# HW-DC25-Badge-20170609-1_2.net
KiCad netlist of a schematic drawn in EAGLE
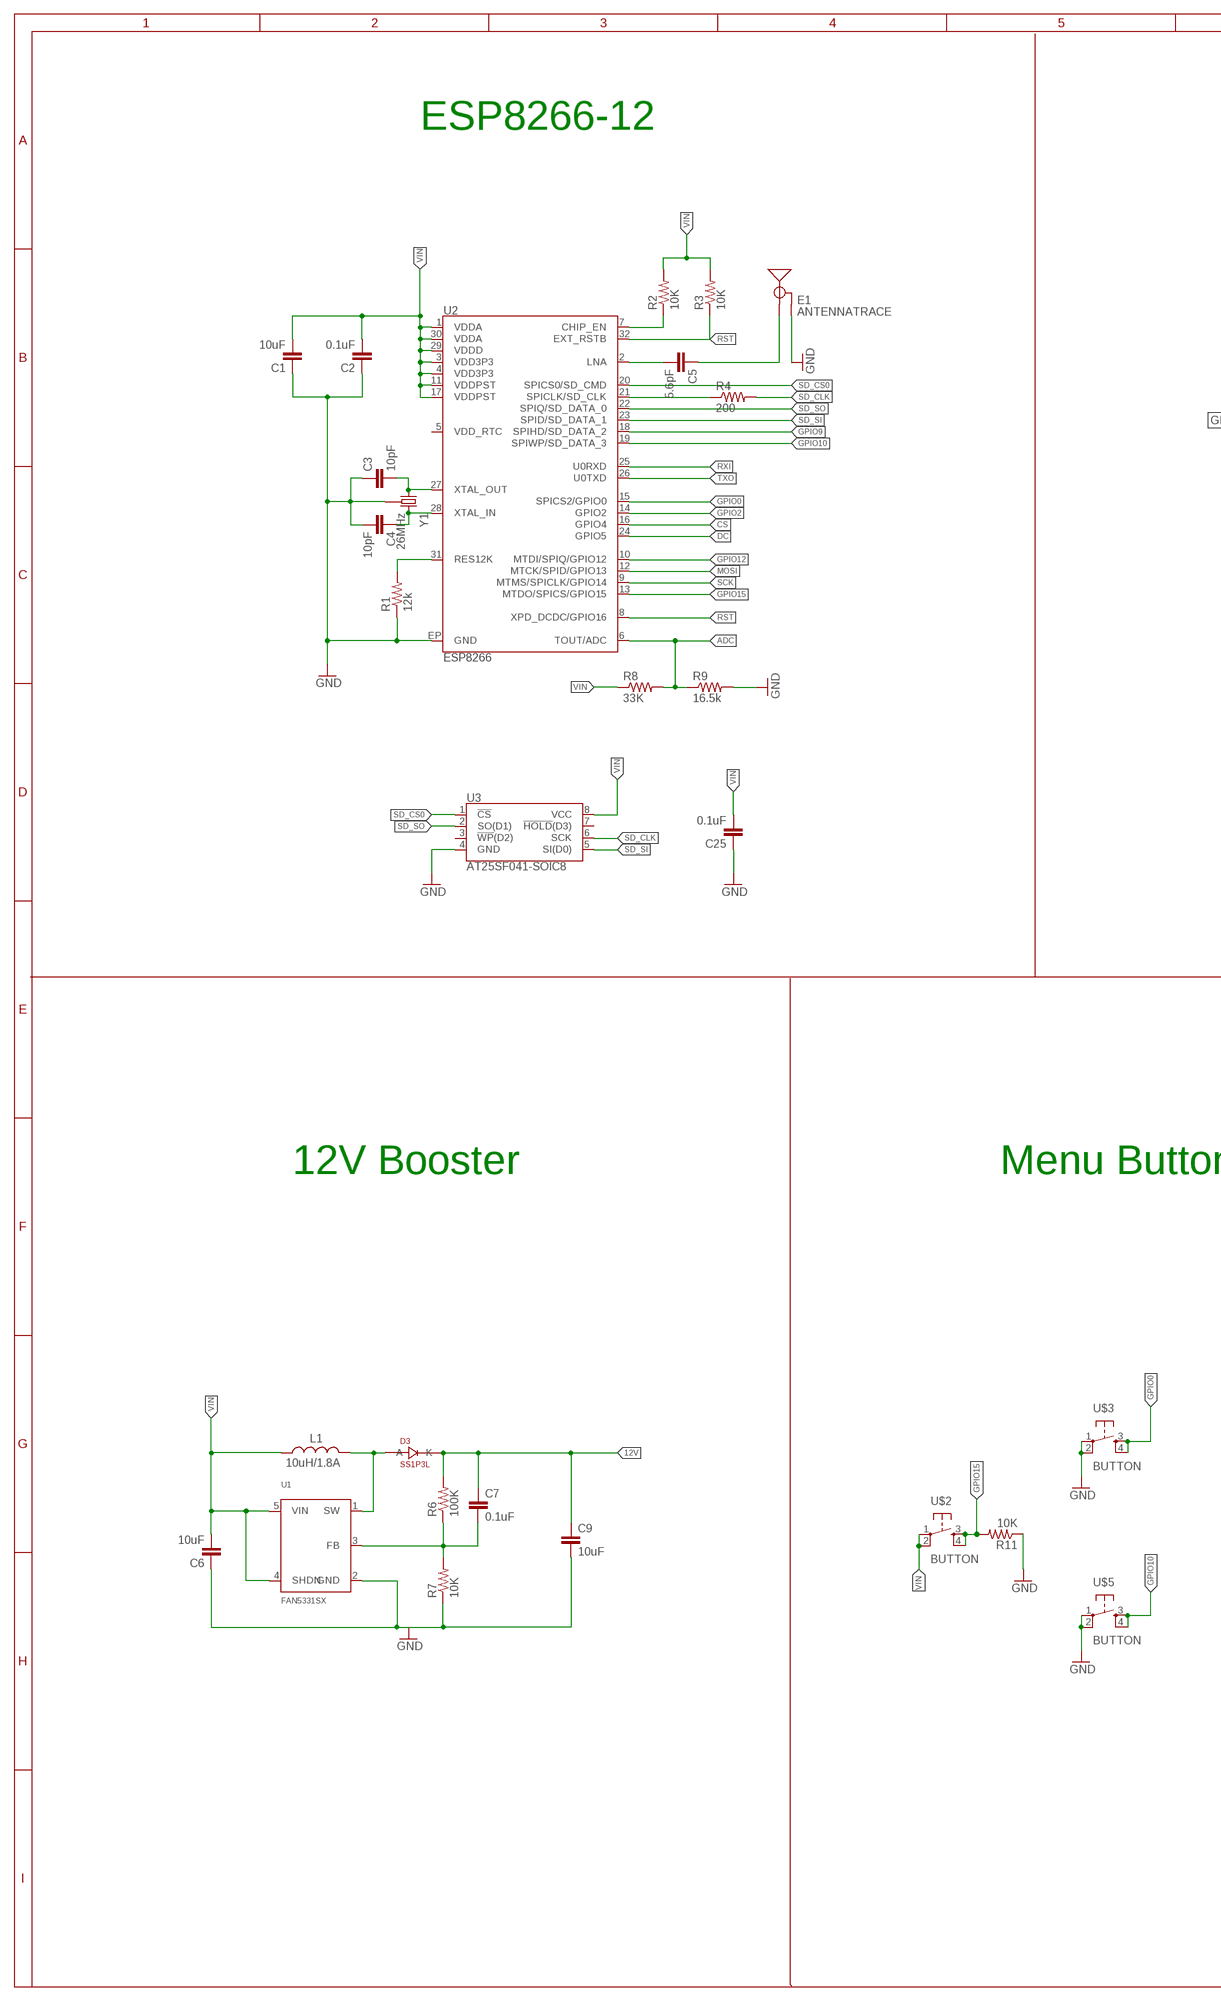
[diagram p0: schematic, sheet 1, part 1 of 2]
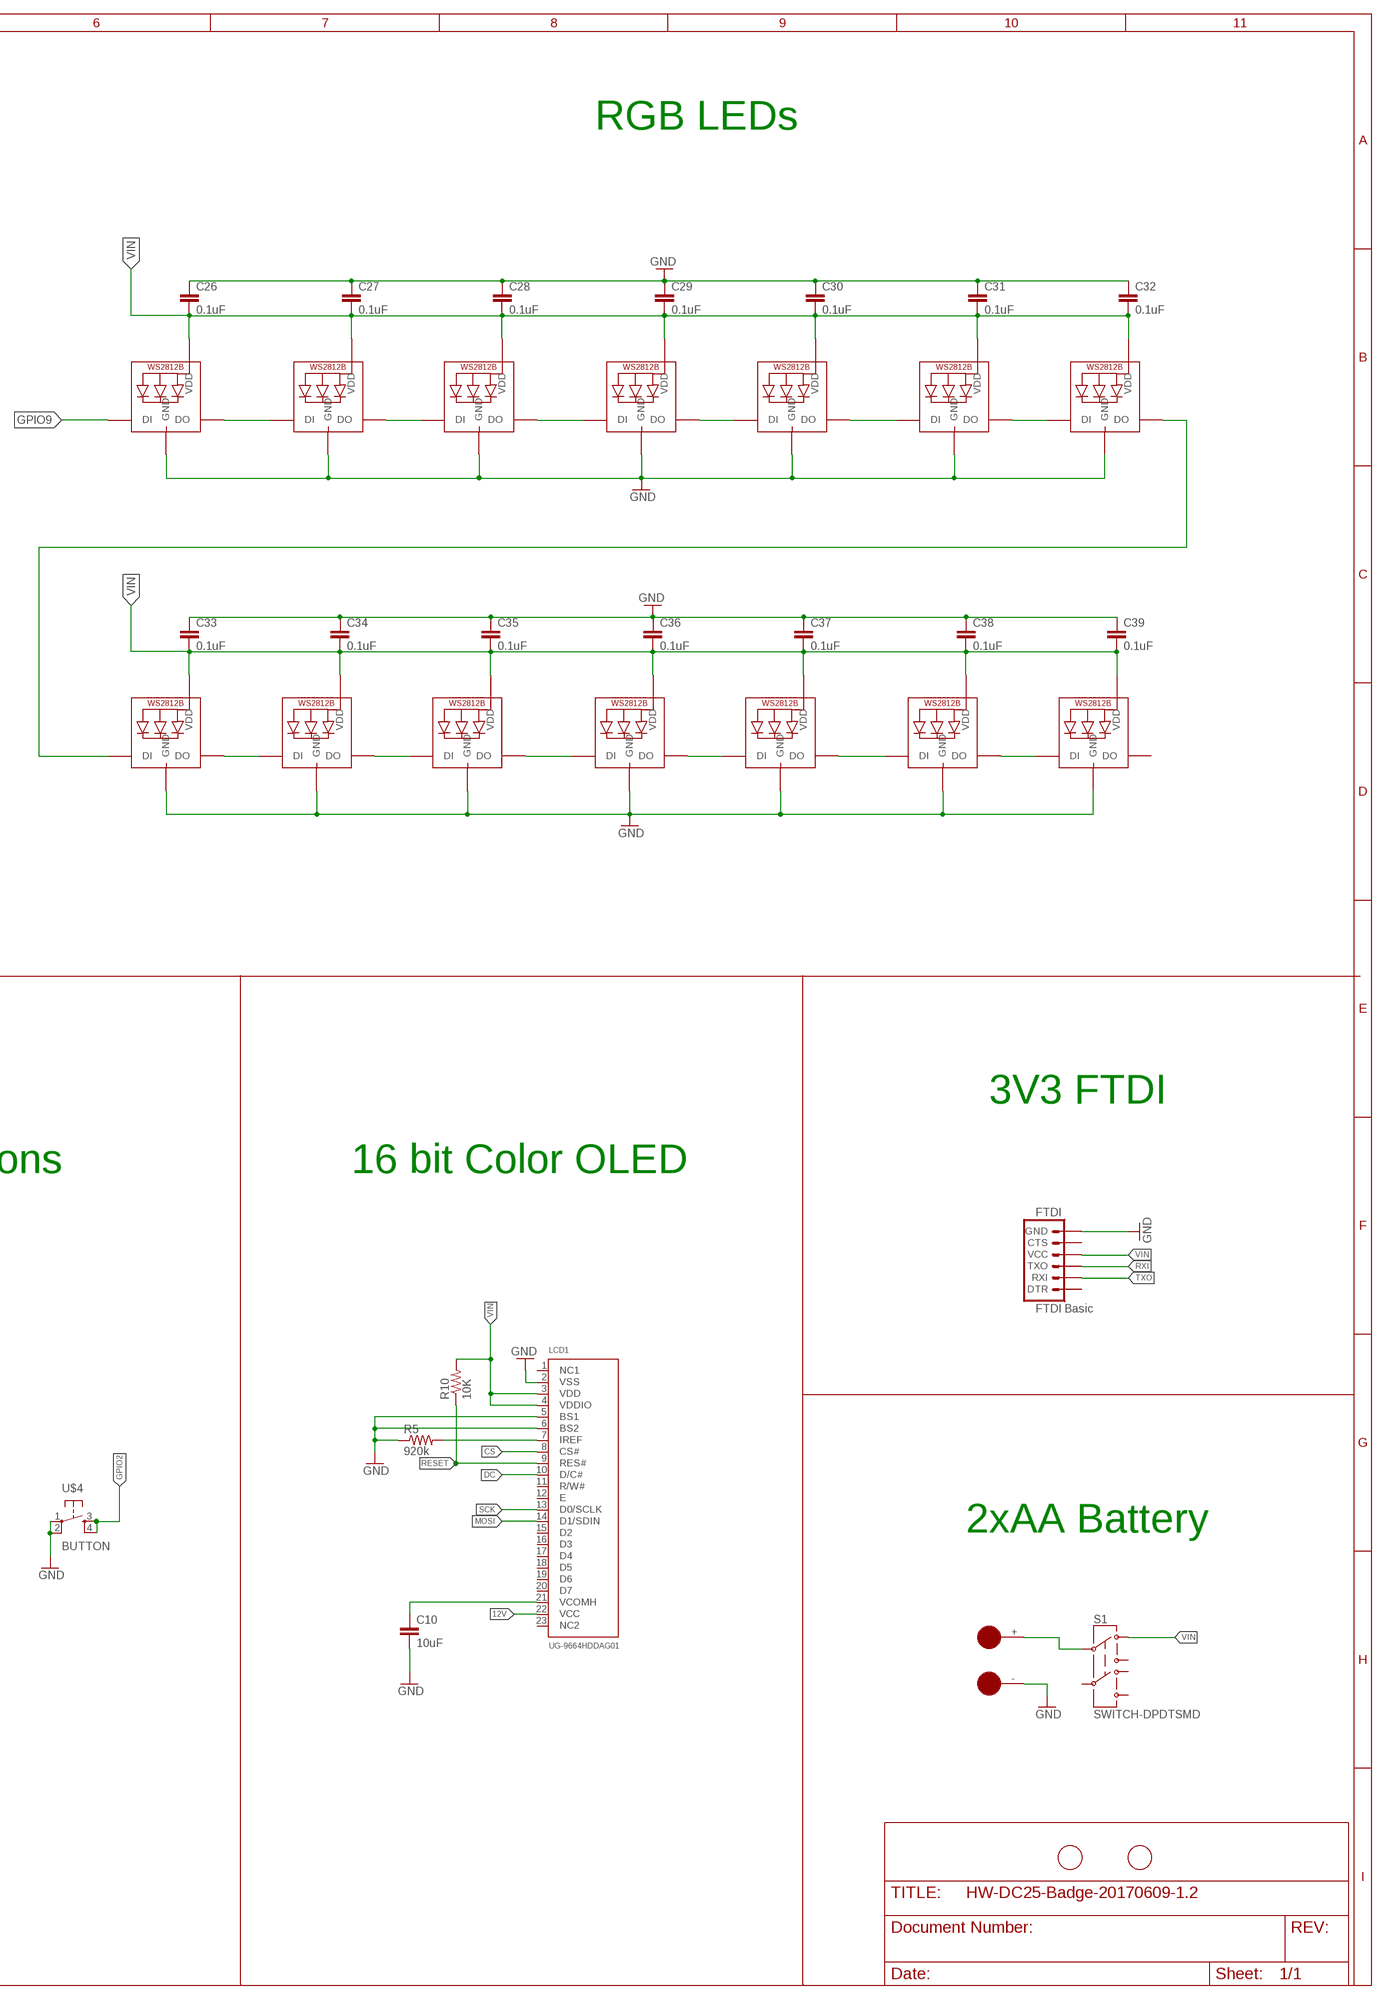
[diagram p1: schematic, sheet 1, part 2 of 2]

(export (version "E")
  (design (tool "Eeschema 10.0.6"))
  (components
    (comp (ref "C1")
      (value "10uF")
      (footprint "eagle-import:CAP0603")
      (fields (field (name "TOLERANCE") "10%") (field (name "VOLTAGE") "10V"))
      (libsource (lib "eagle-import") (part "CAP-0603-10UF-10V-10%"))
    )
    (comp (ref "C2")
      (value "0.1uF")
      (footprint "eagle-import:CAP0603")
      (fields (field (name "TOLERANCE") "10%") (field (name "VOLTAGE") "10V"))
      (libsource (lib "eagle-import") (part "CAP-0603-10UF-10V-10%"))
    )
    (comp (ref "C3")
      (value "10pF")
      (footprint "eagle-import:CAP0603")
      (fields (field (name "TOLERANCE") "10%") (field (name "VOLTAGE") "50V"))
      (libsource (lib "eagle-import") (part "CAP-0603-0.01UF-50V-10%"))
    )
    (comp (ref "C4")
      (value "10pF")
      (footprint "eagle-import:CAP0603")
      (fields (field (name "TOLERANCE") "10%") (field (name "VOLTAGE") "50V"))
      (libsource (lib "eagle-import") (part "CAP-0603-0.01UF-50V-10%"))
    )
    (comp (ref "C5")
      (value "5.6pF")
      (footprint "eagle-import:CAP0603")
      (libsource (lib "eagle-import") (part "CAP-0603-EMPTY-VALUES"))
    )
    (comp (ref "C6")
      (value "10uF")
      (footprint "eagle-import:CAP0603")
      (fields (field (name "TOLERANCE") "10%") (field (name "VOLTAGE") "10V"))
      (libsource (lib "eagle-import") (part "CAP-0603-10UF-10V-10%"))
    )
    (comp (ref "C7")
      (value "0.1uF")
      (footprint "eagle-import:CAP0603")
      (fields (field (name "TOLERANCE") "10%") (field (name "VOLTAGE") "25V"))
      (libsource (lib "eagle-import") (part "CAP-0603-0.1UF-25V-10%"))
    )
    (comp (ref "C9")
      (value "10uF")
      (footprint "eagle-import:CAP0603")
      (fields (field (name "TOLERANCE") "20%") (field (name "VOLTAGE") "25V"))
      (libsource (lib "eagle-import") (part "CAP-0603-10UF-25V-20%"))
    )
    (comp (ref "C10")
      (value "10uF")
      (footprint "eagle-import:CAP0603")
      (fields (field (name "TOLERANCE") "20%") (field (name "VOLTAGE") "25V"))
      (libsource (lib "eagle-import") (part "CAP-0603-10UF-25V-20%"))
    )
    (comp (ref "C25")
      (value "0.1uF")
      (footprint "eagle-import:CAP0603")
      (fields (field (name "TOLERANCE") "10%") (field (name "VOLTAGE") "10V"))
      (libsource (lib "eagle-import") (part "CAP-0603-10UF-10V-10%"))
    )
    (comp (ref "C26")
      (value "0.1uF")
      (footprint "eagle-import:CAP0402")
      (fields (field (name "TOLERANCE") "10%") (field (name "VOLTAGE") "16V"))
      (libsource (lib "eagle-import") (part "CAP-0402-0.1UF-16V-10%"))
    )
    (comp (ref "C27")
      (value "0.1uF")
      (footprint "eagle-import:CAP0402")
      (fields (field (name "TOLERANCE") "10%") (field (name "VOLTAGE") "16V"))
      (libsource (lib "eagle-import") (part "CAP-0402-0.1UF-16V-10%"))
    )
    (comp (ref "C28")
      (value "0.1uF")
      (footprint "eagle-import:CAP0402")
      (fields (field (name "TOLERANCE") "10%") (field (name "VOLTAGE") "16V"))
      (libsource (lib "eagle-import") (part "CAP-0402-0.1UF-16V-10%"))
    )
    (comp (ref "C29")
      (value "0.1uF")
      (footprint "eagle-import:CAP0402")
      (fields (field (name "TOLERANCE") "10%") (field (name "VOLTAGE") "16V"))
      (libsource (lib "eagle-import") (part "CAP-0402-0.1UF-16V-10%"))
    )
    (comp (ref "C30")
      (value "0.1uF")
      (footprint "eagle-import:CAP0402")
      (fields (field (name "TOLERANCE") "10%") (field (name "VOLTAGE") "16V"))
      (libsource (lib "eagle-import") (part "CAP-0402-0.1UF-16V-10%"))
    )
    (comp (ref "C31")
      (value "0.1uF")
      (footprint "eagle-import:CAP0402")
      (fields (field (name "TOLERANCE") "10%") (field (name "VOLTAGE") "16V"))
      (libsource (lib "eagle-import") (part "CAP-0402-0.1UF-16V-10%"))
    )
    (comp (ref "C32")
      (value "0.1uF")
      (footprint "eagle-import:CAP0402")
      (fields (field (name "TOLERANCE") "10%") (field (name "VOLTAGE") "16V"))
      (libsource (lib "eagle-import") (part "CAP-0402-0.1UF-16V-10%"))
    )
    (comp (ref "C33")
      (value "0.1uF")
      (footprint "eagle-import:CAP0402")
      (fields (field (name "TOLERANCE") "10%") (field (name "VOLTAGE") "16V"))
      (libsource (lib "eagle-import") (part "CAP-0402-0.1UF-16V-10%"))
    )
    (comp (ref "C34")
      (value "0.1uF")
      (footprint "eagle-import:CAP0402")
      (fields (field (name "TOLERANCE") "10%") (field (name "VOLTAGE") "16V"))
      (libsource (lib "eagle-import") (part "CAP-0402-0.1UF-16V-10%"))
    )
    (comp (ref "C35")
      (value "0.1uF")
      (footprint "eagle-import:CAP0402")
      (fields (field (name "TOLERANCE") "10%") (field (name "VOLTAGE") "16V"))
      (libsource (lib "eagle-import") (part "CAP-0402-0.1UF-16V-10%"))
    )
    (comp (ref "C36")
      (value "0.1uF")
      (footprint "eagle-import:CAP0402")
      (fields (field (name "TOLERANCE") "10%") (field (name "VOLTAGE") "16V"))
      (libsource (lib "eagle-import") (part "CAP-0402-0.1UF-16V-10%"))
    )
    (comp (ref "C37")
      (value "0.1uF")
      (footprint "eagle-import:CAP0402")
      (fields (field (name "TOLERANCE") "10%") (field (name "VOLTAGE") "16V"))
      (libsource (lib "eagle-import") (part "CAP-0402-0.1UF-16V-10%"))
    )
    (comp (ref "C38")
      (value "0.1uF")
      (footprint "eagle-import:CAP0402")
      (fields (field (name "TOLERANCE") "10%") (field (name "VOLTAGE") "16V"))
      (libsource (lib "eagle-import") (part "CAP-0402-0.1UF-16V-10%"))
    )
    (comp (ref "C39")
      (value "0.1uF")
      (footprint "eagle-import:CAP0402")
      (fields (field (name "TOLERANCE") "10%") (field (name "VOLTAGE") "16V"))
      (libsource (lib "eagle-import") (part "CAP-0402-0.1UF-16V-10%"))
    )
    (comp (ref "D3")
      (value "SS1P3L")
      (footprint "eagle-import:DO220AAL")
      (libsource (lib "eagle-import") (part "SS1P3L"))
    )
    (comp (ref "E1")
      (value "ANTENNATRACE")
      (footprint "eagle-import:TRACE_ANTENNA_2.4GHZ_25.7MM")
      (libsource (lib "eagle-import") (part "ANTENNATRACE"))
    )
    (comp (ref "FTDI")
      (value "FTDI Basic")
      (footprint "eagle-import:1X06")
      (libsource (lib "eagle-import") (part "ARDUINO_SERIAL_PROGRAMPTH"))
    )
    (comp (ref "L1")
      (value "10uH/1.8A")
      (footprint "eagle-import:SRU5028")
      (libsource (lib "eagle-import") (part "INDUCTORSRU5028"))
    )
    (comp (ref "LCD1")
      (value "UG-9664HDDAG01")
      (footprint "eagle-import:UG-9664HDDAG01_WRAPAROUND")
      (libsource (lib "eagle-import") (part "DISP_OLED_UG-9664HDDAG01WRAPAROUND"))
    )
    (comp (ref "LED1")
      (value "WS2812B3535")
      (footprint "eagle-import:LED3535")
      (libsource (lib "eagle-import") (part "WS2812B3535"))
    )
    (comp (ref "LED2")
      (value "WS2812B3535")
      (footprint "eagle-import:LED3535")
      (libsource (lib "eagle-import") (part "WS2812B3535"))
    )
    (comp (ref "LED3")
      (value "WS2812B3535")
      (footprint "eagle-import:LED3535")
      (libsource (lib "eagle-import") (part "WS2812B3535"))
    )
    (comp (ref "LED4")
      (value "WS2812B3535")
      (footprint "eagle-import:LED3535")
      (libsource (lib "eagle-import") (part "WS2812B3535"))
    )
    (comp (ref "LED5")
      (value "WS2812B3535")
      (footprint "eagle-import:LED3535")
      (libsource (lib "eagle-import") (part "WS2812B3535"))
    )
    (comp (ref "LED6")
      (value "WS2812B3535")
      (footprint "eagle-import:LED3535")
      (libsource (lib "eagle-import") (part "WS2812B3535"))
    )
    (comp (ref "LED7")
      (value "WS2812B3535")
      (footprint "eagle-import:LED3535")
      (libsource (lib "eagle-import") (part "WS2812B3535"))
    )
    (comp (ref "LED8")
      (value "WS2812B3535")
      (footprint "eagle-import:LED3535")
      (libsource (lib "eagle-import") (part "WS2812B3535"))
    )
    (comp (ref "LED9")
      (value "WS2812B3535")
      (footprint "eagle-import:LED3535")
      (libsource (lib "eagle-import") (part "WS2812B3535"))
    )
    (comp (ref "LED10")
      (value "WS2812B3535")
      (footprint "eagle-import:LED3535")
      (libsource (lib "eagle-import") (part "WS2812B3535"))
    )
    (comp (ref "LED11")
      (value "WS2812B3535")
      (footprint "eagle-import:LED3535")
      (libsource (lib "eagle-import") (part "WS2812B3535"))
    )
    (comp (ref "LED12")
      (value "WS2812B3535")
      (footprint "eagle-import:LED3535")
      (libsource (lib "eagle-import") (part "WS2812B3535"))
    )
    (comp (ref "LED13")
      (value "WS2812B3535")
      (footprint "eagle-import:LED3535")
      (libsource (lib "eagle-import") (part "WS2812B3535"))
    )
    (comp (ref "LED14")
      (value "WS2812B3535")
      (footprint "eagle-import:LED3535")
      (libsource (lib "eagle-import") (part "WS2812B3535"))
    )
    (comp (ref "R1")
      (value "12k")
      (footprint "eagle-import:RES-0603")
      (libsource (lib "eagle-import") (part "RES-0603_EMPTY-FIELDS"))
    )
    (comp (ref "R2")
      (value "10K")
      (footprint "eagle-import:RES-0603")
      (fields (field (name "TOLERANCE") "5%"))
      (libsource (lib "eagle-import") (part "RES-0603-10K-5%"))
    )
    (comp (ref "R3")
      (value "10K")
      (footprint "eagle-import:RES-0603")
      (fields (field (name "TOLERANCE") "5%"))
      (libsource (lib "eagle-import") (part "RES-0603-10K-5%"))
    )
    (comp (ref "R4")
      (value "200")
      (footprint "eagle-import:RES-0603")
      (libsource (lib "eagle-import") (part "RES-0603_EMPTY-FIELDS"))
    )
    (comp (ref "R5")
      (value "920k")
      (footprint "eagle-import:RES-0603")
      (libsource (lib "eagle-import") (part "RES-0603_EMPTY-FIELDS"))
    )
    (comp (ref "R6")
      (value "100K")
      (footprint "eagle-import:RES-0603")
      (fields (field (name "TOLERANCE") "5%"))
      (libsource (lib "eagle-import") (part "RES-0603-100K-5%"))
    )
    (comp (ref "R7")
      (value "10K")
      (footprint "eagle-import:RES-0603")
      (fields (field (name "TOLERANCE") "5%"))
      (libsource (lib "eagle-import") (part "RES-0603-10K-5%"))
    )
    (comp (ref "R8")
      (value "33K")
      (footprint "eagle-import:RES-0603")
      (fields (field (name "TOLERANCE") "1%"))
      (libsource (lib "eagle-import") (part "RES-0603-33K-1%"))
    )
    (comp (ref "R9")
      (value "16.5k")
      (footprint "eagle-import:RES-0603")
      (fields (field (name "TOLERANCE") "5%"))
      (libsource (lib "eagle-import") (part "RES-0603-10K-5%"))
    )
    (comp (ref "R10")
      (value "10K")
      (footprint "eagle-import:RES-0603")
      (fields (field (name "TOLERANCE") "5%"))
      (libsource (lib "eagle-import") (part "RES-0603-10K-5%"))
    )
    (comp (ref "R11")
      (value "10K")
      (footprint "eagle-import:RES-0603")
      (fields (field (name "TOLERANCE") "5%"))
      (libsource (lib "eagle-import") (part "RES-0603-10K-5%"))
    )
    (comp (ref "S1")
      (value "SWITCH-DPDTSMD")
      (footprint "eagle-import:AYZ0202")
      (libsource (lib "eagle-import") (part "SWITCH-DPDTSMD"))
    )
    (comp (ref "U$1")
      (value "BAT_HOLD")
      (footprint "eagle-import:AA")
      (libsource (lib "eagle-import") (part "BAT_HOLD"))
    )
    (comp (ref "U$2")
      (value "BUTTON")
      (footprint "eagle-import:BUTTON")
      (libsource (lib "eagle-import") (part "BUTTON"))
    )
    (comp (ref "U$3")
      (value "BUTTON")
      (footprint "eagle-import:BUTTON")
      (libsource (lib "eagle-import") (part "BUTTON"))
    )
    (comp (ref "U$4")
      (value "BUTTON")
      (footprint "eagle-import:BUTTON")
      (libsource (lib "eagle-import") (part "BUTTON"))
    )
    (comp (ref "U$5")
      (value "BUTTON")
      (footprint "eagle-import:BUTTON")
      (libsource (lib "eagle-import") (part "BUTTON"))
    )
    (comp (ref "U$6")
      (value "FIDUCIAL")
      (footprint "eagle-import:FIDUCIAL_1MM")
      (libsource (lib "eagle-import") (part "FIDUCIAL"))
    )
    (comp (ref "U$7")
      (value "FIDUCIAL")
      (footprint "eagle-import:FIDUCIAL_1MM")
      (libsource (lib "eagle-import") (part "FIDUCIAL"))
    )
    (comp (ref "U1")
      (value "FAN5331SX")
      (footprint "eagle-import:SOT23-5")
      (libsource (lib "eagle-import") (part "FAN5331"))
    )
    (comp (ref "U2")
      (value "ESP8266")
      (footprint "eagle-import:QFN32")
      (libsource (lib "eagle-import") (part "ESP8266"))
    )
    (comp (ref "U3")
      (value "AT25SF041-SOIC8")
      (footprint "eagle-import:SO08")
      (libsource (lib "eagle-import") (part "AT25SF041-SOIC8"))
    )
    (comp (ref "Y1")
      (value "26MHz")
      (footprint "eagle-import:CRYSTAL-SMD-3.2X2.5")
      (libsource (lib "eagle-import") (part "CRYSTAL-GROUNDED3.2X2.5"))
    )
  )
  (nets
    (net (code "1") (name "12V") (class "Default")
      (node (ref "C7") (pin "1") (pinfunction "1_1") (pintype "passive"))
      (node (ref "C9") (pin "1") (pinfunction "1_1") (pintype "passive"))
      (node (ref "D3") (pin "P$1") (pinfunction "K_P$1") (pintype "bidirectional"))
      (node (ref "LCD1") (pin "22") (pinfunction "VCC_22") (pintype "bidirectional"))
      (node (ref "R6") (pin "2") (pinfunction "2_2") (pintype "passive"))
    )
    (net (code "2") (name "ADC") (class "Default")
      (node (ref "R8") (pin "2") (pinfunction "2_2") (pintype "passive"))
      (node (ref "R9") (pin "1") (pinfunction "1_1") (pintype "passive"))
      (node (ref "U2") (pin "6") (pinfunction "TOUT/ADC_6") (pintype "bidirectional"))
    )
    (net (code "3") (name "CS") (class "Default")
      (node (ref "LCD1") (pin "8") (pinfunction "CS#_8") (pintype "bidirectional"))
      (node (ref "U2") (pin "16") (pinfunction "GPIO4_16") (pintype "bidirectional"))
    )
    (net (code "4") (name "DC") (class "Default")
      (node (ref "LCD1") (pin "10") (pinfunction "D/C#_10") (pintype "bidirectional"))
      (node (ref "U2") (pin "24") (pinfunction "GPIO5_24") (pintype "bidirectional"))
    )
    (net (code "5") (name "GND") (class "Default")
      (node (ref "C1") (pin "1") (pinfunction "1_1") (pintype "passive"))
      (node (ref "C10") (pin "2") (pinfunction "2_2") (pintype "passive"))
      (node (ref "C2") (pin "1") (pinfunction "1_1") (pintype "passive"))
      (node (ref "C25") (pin "1") (pinfunction "1_1") (pintype "passive"))
      (node (ref "C26") (pin "P$1") (pinfunction "1_P$1") (pintype "passive"))
      (node (ref "C27") (pin "P$1") (pinfunction "1_P$1") (pintype "passive"))
      (node (ref "C28") (pin "P$1") (pinfunction "1_P$1") (pintype "passive"))
      (node (ref "C29") (pin "P$1") (pinfunction "1_P$1") (pintype "passive"))
      (node (ref "C3") (pin "1") (pinfunction "1_1") (pintype "passive"))
      (node (ref "C30") (pin "P$1") (pinfunction "1_P$1") (pintype "passive"))
      (node (ref "C31") (pin "P$1") (pinfunction "1_P$1") (pintype "passive"))
      (node (ref "C32") (pin "P$1") (pinfunction "1_P$1") (pintype "passive"))
      (node (ref "C33") (pin "P$1") (pinfunction "1_P$1") (pintype "passive"))
      (node (ref "C34") (pin "P$1") (pinfunction "1_P$1") (pintype "passive"))
      (node (ref "C35") (pin "P$1") (pinfunction "1_P$1") (pintype "passive"))
      (node (ref "C36") (pin "P$1") (pinfunction "1_P$1") (pintype "passive"))
      (node (ref "C37") (pin "P$1") (pinfunction "1_P$1") (pintype "passive"))
      (node (ref "C38") (pin "P$1") (pinfunction "1_P$1") (pintype "passive"))
      (node (ref "C39") (pin "P$1") (pinfunction "1_P$1") (pintype "passive"))
      (node (ref "C4") (pin "2") (pinfunction "2_2") (pintype "passive"))
      (node (ref "C6") (pin "1") (pinfunction "1_1") (pintype "passive"))
      (node (ref "C9") (pin "2") (pinfunction "2_2") (pintype "passive"))
      (node (ref "E1") (pin "GND") (pinfunction "GND_GND") (pintype "bidirectional"))
      (node (ref "E1") (pin "GND2") (pinfunction "GND_GND2") (pintype "bidirectional"))
      (node (ref "FTDI") (pin "6") (pinfunction "GND_6") (pintype "passive"))
      (node (ref "LCD1") (pin "2") (pinfunction "VSS_2") (pintype "bidirectional"))
      (node (ref "LCD1") (pin "5") (pinfunction "BS1_5") (pintype "bidirectional"))
      (node (ref "LCD1") (pin "6") (pinfunction "BS2_6") (pintype "bidirectional"))
      (node (ref "LED1") (pin "4") (pinfunction "GND_4") (pintype "power_in"))
      (node (ref "LED10") (pin "4") (pinfunction "GND_4") (pintype "power_in"))
      (node (ref "LED11") (pin "4") (pinfunction "GND_4") (pintype "power_in"))
      (node (ref "LED12") (pin "4") (pinfunction "GND_4") (pintype "power_in"))
      (node (ref "LED13") (pin "4") (pinfunction "GND_4") (pintype "power_in"))
      (node (ref "LED14") (pin "4") (pinfunction "GND_4") (pintype "power_in"))
      (node (ref "LED2") (pin "4") (pinfunction "GND_4") (pintype "power_in"))
      (node (ref "LED3") (pin "4") (pinfunction "GND_4") (pintype "power_in"))
      (node (ref "LED4") (pin "4") (pinfunction "GND_4") (pintype "power_in"))
      (node (ref "LED5") (pin "4") (pinfunction "GND_4") (pintype "power_in"))
      (node (ref "LED6") (pin "4") (pinfunction "GND_4") (pintype "power_in"))
      (node (ref "LED7") (pin "4") (pinfunction "GND_4") (pintype "power_in"))
      (node (ref "LED8") (pin "4") (pinfunction "GND_4") (pintype "power_in"))
      (node (ref "LED9") (pin "4") (pinfunction "GND_4") (pintype "power_in"))
      (node (ref "R1") (pin "1") (pinfunction "1_1") (pintype "passive"))
      (node (ref "R11") (pin "1") (pinfunction "1_1") (pintype "passive"))
      (node (ref "R5") (pin "1") (pinfunction "1_1") (pintype "passive"))
      (node (ref "R7") (pin "1") (pinfunction "1_1") (pintype "passive"))
      (node (ref "R9") (pin "2") (pinfunction "2_2") (pintype "passive"))
      (node (ref "U$1") (pin "-") (pinfunction "-_-") (pintype "bidirectional"))
      (node (ref "U$3") (pin "1") (pinfunction "1_1") (pintype "passive"))
      (node (ref "U$3") (pin "2") (pinfunction "2_2") (pintype "passive"))
      (node (ref "U$4") (pin "1") (pinfunction "1_1") (pintype "passive"))
      (node (ref "U$4") (pin "2") (pinfunction "2_2") (pintype "passive"))
      (node (ref "U$5") (pin "1") (pinfunction "1_1") (pintype "passive"))
      (node (ref "U$5") (pin "2") (pinfunction "2_2") (pintype "passive"))
      (node (ref "U1") (pin "2") (pinfunction "GND_2") (pintype "bidirectional"))
      (node (ref "U2") (pin "EP") (pinfunction "GND_EP") (pintype "bidirectional"))
      (node (ref "U3") (pin "4") (pinfunction "GND_4") (pintype "bidirectional"))
      (node (ref "Y1") (pin "2") (pinfunction "GND_2") (pintype "passive"))
      (node (ref "Y1") (pin "4") (pinfunction "GND_4") (pintype "passive"))
    )
    (net (code "6") (name "GPIO0") (class "Default")
      (node (ref "U$3") (pin "3") (pinfunction "3_3") (pintype "passive"))
      (node (ref "U$3") (pin "4") (pinfunction "4_4") (pintype "passive"))
      (node (ref "U2") (pin "15") (pinfunction "SPICS2/GPIO0_15") (pintype "bidirectional"))
    )
    (net (code "7") (name "GPIO2") (class "Default")
      (node (ref "U$4") (pin "3") (pinfunction "3_3") (pintype "passive"))
      (node (ref "U$4") (pin "4") (pinfunction "4_4") (pintype "passive"))
      (node (ref "U2") (pin "14") (pinfunction "GPIO2_14") (pintype "bidirectional"))
    )
    (net (code "8") (name "GPIO9") (class "Default")
      (node (ref "LED1") (pin "1") (pinfunction "DI_1") (pintype "input"))
      (node (ref "U2") (pin "18") (pinfunction "SPIHD/SD_DATA_2_18") (pintype "bidirectional"))
    )
    (net (code "9") (name "GPIO10") (class "Default")
      (node (ref "U$5") (pin "3") (pinfunction "3_3") (pintype "passive"))
      (node (ref "U$5") (pin "4") (pinfunction "4_4") (pintype "passive"))
      (node (ref "U2") (pin "19") (pinfunction "SPIWP/SD_DATA_3_19") (pintype "bidirectional"))
    )
    (net (code "10") (name "GPIO12") (class "Default")
      (node (ref "U2") (pin "10") (pinfunction "MTDI/SPIQ/GPIO12_10") (pintype "bidirectional"))
    )
    (net (code "11") (name "GPIO15") (class "Default")
      (node (ref "R11") (pin "2") (pinfunction "2_2") (pintype "passive"))
      (node (ref "U$2") (pin "3") (pinfunction "3_3") (pintype "passive"))
      (node (ref "U$2") (pin "4") (pinfunction "4_4") (pintype "passive"))
      (node (ref "U2") (pin "13") (pinfunction "MTDO/SPICS/GPIO15_13") (pintype "bidirectional"))
    )
    (net (code "12") (name "MOSI") (class "Default")
      (node (ref "LCD1") (pin "14") (pinfunction "D1/SDIN_14") (pintype "bidirectional"))
      (node (ref "U2") (pin "12") (pinfunction "MTCK/SPID/GPIO13_12") (pintype "bidirectional"))
    )
    (net (code "13") (name "Net-(D3-A)") (class "Default")
      (node (ref "D3") (pin "P$2") (pinfunction "A_P$2") (pintype "bidirectional"))
      (node (ref "L1") (pin "2") (pinfunction "2_2") (pintype "passive"))
      (node (ref "U1") (pin "1") (pinfunction "SW_1") (pintype "bidirectional"))
    )
    (net (code "14") (name "Net-(E1-SIGNAL)") (class "Default")
      (node (ref "C5") (pin "1") (pinfunction "1_1") (pintype "passive"))
      (node (ref "E1") (pin "ANT") (pinfunction "SIGNAL_ANT") (pintype "bidirectional"))
    )
    (net (code "15") (name "Net-(LCD1-IREF)") (class "Default")
      (node (ref "LCD1") (pin "7") (pinfunction "IREF_7") (pintype "bidirectional"))
      (node (ref "R5") (pin "2") (pinfunction "2_2") (pintype "passive"))
    )
    (net (code "16") (name "Net-(LCD1-VCOMH)") (class "Default")
      (node (ref "C10") (pin "1") (pinfunction "1_1") (pintype "passive"))
      (node (ref "LCD1") (pin "21") (pinfunction "VCOMH_21") (pintype "bidirectional"))
    )
    (net (code "17") (name "Net-(LED1-DO)") (class "Default")
      (node (ref "LED1") (pin "3") (pinfunction "DO_3") (pintype "output"))
      (node (ref "LED2") (pin "1") (pinfunction "DI_1") (pintype "input"))
    )
    (net (code "18") (name "Net-(LED2-DO)") (class "Default")
      (node (ref "LED2") (pin "3") (pinfunction "DO_3") (pintype "output"))
      (node (ref "LED3") (pin "1") (pinfunction "DI_1") (pintype "input"))
    )
    (net (code "19") (name "Net-(LED3-DO)") (class "Default")
      (node (ref "LED3") (pin "3") (pinfunction "DO_3") (pintype "output"))
      (node (ref "LED4") (pin "1") (pinfunction "DI_1") (pintype "input"))
    )
    (net (code "20") (name "Net-(LED4-DO)") (class "Default")
      (node (ref "LED4") (pin "3") (pinfunction "DO_3") (pintype "output"))
      (node (ref "LED5") (pin "1") (pinfunction "DI_1") (pintype "input"))
    )
    (net (code "21") (name "Net-(LED5-DO)") (class "Default")
      (node (ref "LED5") (pin "3") (pinfunction "DO_3") (pintype "output"))
      (node (ref "LED6") (pin "1") (pinfunction "DI_1") (pintype "input"))
    )
    (net (code "22") (name "Net-(LED6-DO)") (class "Default")
      (node (ref "LED6") (pin "3") (pinfunction "DO_3") (pintype "output"))
      (node (ref "LED7") (pin "1") (pinfunction "DI_1") (pintype "input"))
    )
    (net (code "23") (name "Net-(LED7-DO)") (class "Default")
      (node (ref "LED7") (pin "3") (pinfunction "DO_3") (pintype "output"))
      (node (ref "LED8") (pin "1") (pinfunction "DI_1") (pintype "input"))
    )
    (net (code "24") (name "Net-(LED8-DO)") (class "Default")
      (node (ref "LED8") (pin "3") (pinfunction "DO_3") (pintype "output"))
      (node (ref "LED9") (pin "1") (pinfunction "DI_1") (pintype "input"))
    )
    (net (code "25") (name "Net-(LED10-DI)") (class "Default")
      (node (ref "LED10") (pin "1") (pinfunction "DI_1") (pintype "input"))
      (node (ref "LED9") (pin "3") (pinfunction "DO_3") (pintype "output"))
    )
    (net (code "26") (name "Net-(LED10-DO)") (class "Default")
      (node (ref "LED10") (pin "3") (pinfunction "DO_3") (pintype "output"))
      (node (ref "LED11") (pin "1") (pinfunction "DI_1") (pintype "input"))
    )
    (net (code "27") (name "Net-(LED11-DO)") (class "Default")
      (node (ref "LED11") (pin "3") (pinfunction "DO_3") (pintype "output"))
      (node (ref "LED12") (pin "1") (pinfunction "DI_1") (pintype "input"))
    )
    (net (code "28") (name "Net-(LED12-DO)") (class "Default")
      (node (ref "LED12") (pin "3") (pinfunction "DO_3") (pintype "output"))
      (node (ref "LED13") (pin "1") (pinfunction "DI_1") (pintype "input"))
    )
    (net (code "29") (name "Net-(LED13-DO)") (class "Default")
      (node (ref "LED13") (pin "3") (pinfunction "DO_3") (pintype "output"))
      (node (ref "LED14") (pin "1") (pinfunction "DI_1") (pintype "input"))
    )
    (net (code "30") (name "Net-(S1-Pad2)") (class "Default")
      (node (ref "S1") (pin "2") (pinfunction "2_2") (pintype "bidirectional"))
      (node (ref "U$1") (pin "+") (pinfunction "+_+") (pintype "bidirectional"))
    )
    (net (code "31") (name "Net-(U1-FB)") (class "Default")
      (node (ref "C7") (pin "2") (pinfunction "2_2") (pintype "passive"))
      (node (ref "R6") (pin "1") (pinfunction "1_1") (pintype "passive"))
      (node (ref "R7") (pin "2") (pinfunction "2_2") (pintype "passive"))
      (node (ref "U1") (pin "3") (pinfunction "FB_3") (pintype "bidirectional"))
    )
    (net (code "32") (name "Net-(U2-CHIP_EN)") (class "Default")
      (node (ref "R2") (pin "1") (pinfunction "1_1") (pintype "passive"))
      (node (ref "U2") (pin "7") (pinfunction "CHIP_EN_7") (pintype "bidirectional"))
    )
    (net (code "33") (name "Net-(U2-LNA)") (class "Default")
      (node (ref "C5") (pin "2") (pinfunction "2_2") (pintype "passive"))
      (node (ref "U2") (pin "2") (pinfunction "LNA_2") (pintype "bidirectional"))
    )
    (net (code "34") (name "Net-(U2-RES12K)") (class "Default")
      (node (ref "R1") (pin "2") (pinfunction "2_2") (pintype "passive"))
      (node (ref "U2") (pin "31") (pinfunction "RES12K_31") (pintype "bidirectional"))
    )
    (net (code "35") (name "Net-(U2-SPICLK{slash}SD_CLK)") (class "Default")
      (node (ref "R4") (pin "1") (pinfunction "1_1") (pintype "passive"))
      (node (ref "U2") (pin "21") (pinfunction "SPICLK/SD_CLK_21") (pintype "bidirectional"))
    )
    (net (code "36") (name "Net-(U2-XTAL_IN)") (class "Default")
      (node (ref "C4") (pin "1") (pinfunction "1_1") (pintype "passive"))
      (node (ref "U2") (pin "28") (pinfunction "XTAL_IN_28") (pintype "bidirectional"))
      (node (ref "Y1") (pin "3") (pinfunction "2_3") (pintype "passive"))
    )
    (net (code "37") (name "Net-(U2-XTAL_OUT)") (class "Default")
      (node (ref "C3") (pin "2") (pinfunction "2_2") (pintype "passive"))
      (node (ref "U2") (pin "27") (pinfunction "XTAL_OUT_27") (pintype "bidirectional"))
      (node (ref "Y1") (pin "1") (pinfunction "1_1") (pintype "passive"))
    )
    (net (code "38") (name "RESET") (class "Default")
      (node (ref "LCD1") (pin "9") (pinfunction "RES#_9") (pintype "bidirectional"))
      (node (ref "R10") (pin "1") (pinfunction "1_1") (pintype "passive"))
    )
    (net (code "39") (name "RST") (class "Default")
      (node (ref "R3") (pin "1") (pinfunction "1_1") (pintype "passive"))
      (node (ref "U2") (pin "32") (pinfunction "EXT_RSTB_32") (pintype "bidirectional"))
      (node (ref "U2") (pin "8") (pinfunction "XPD_DCDC/GPIO16_8") (pintype "bidirectional"))
    )
    (net (code "40") (name "RXI") (class "Default")
      (node (ref "FTDI") (pin "3") (pinfunction "TXO_3") (pintype "passive"))
      (node (ref "U2") (pin "25") (pinfunction "U0RXD_25") (pintype "bidirectional"))
    )
    (net (code "41") (name "SCK") (class "Default")
      (node (ref "LCD1") (pin "13") (pinfunction "D0/SCLK_13") (pintype "bidirectional"))
      (node (ref "U2") (pin "9") (pinfunction "MTMS/SPICLK/GPIO14_9") (pintype "bidirectional"))
    )
    (net (code "42") (name "SD_CLK") (class "Default")
      (node (ref "R4") (pin "2") (pinfunction "2_2") (pintype "passive"))
      (node (ref "U3") (pin "6") (pinfunction "SCK_6") (pintype "bidirectional"))
    )
    (net (code "43") (name "SD_CS0") (class "Default")
      (node (ref "U2") (pin "20") (pinfunction "SPICS0/SD_CMD_20") (pintype "bidirectional"))
      (node (ref "U3") (pin "1") (pinfunction "~{CS}_1") (pintype "bidirectional"))
    )
    (net (code "44") (name "SD_SI") (class "Default")
      (node (ref "U2") (pin "23") (pinfunction "SPID/SD_DATA_1_23") (pintype "bidirectional"))
      (node (ref "U3") (pin "5") (pinfunction "SI(D0)_5") (pintype "bidirectional"))
    )
    (net (code "45") (name "SD_SO") (class "Default")
      (node (ref "U2") (pin "22") (pinfunction "SPIQ/SD_DATA_0_22") (pintype "bidirectional"))
      (node (ref "U3") (pin "2") (pinfunction "SO(D1)_2") (pintype "bidirectional"))
    )
    (net (code "46") (name "TXO") (class "Default")
      (node (ref "FTDI") (pin "2") (pinfunction "RXI_2") (pintype "passive"))
      (node (ref "U2") (pin "26") (pinfunction "U0TXD_26") (pintype "bidirectional"))
    )
    (net (code "47") (name "VIN") (class "Default")
      (node (ref "C1") (pin "2") (pinfunction "2_2") (pintype "passive"))
      (node (ref "C2") (pin "2") (pinfunction "2_2") (pintype "passive"))
      (node (ref "C25") (pin "2") (pinfunction "2_2") (pintype "passive"))
      (node (ref "C26") (pin "P$2") (pinfunction "2_P$2") (pintype "passive"))
      (node (ref "C27") (pin "P$2") (pinfunction "2_P$2") (pintype "passive"))
      (node (ref "C28") (pin "P$2") (pinfunction "2_P$2") (pintype "passive"))
      (node (ref "C29") (pin "P$2") (pinfunction "2_P$2") (pintype "passive"))
      (node (ref "C30") (pin "P$2") (pinfunction "2_P$2") (pintype "passive"))
      (node (ref "C31") (pin "P$2") (pinfunction "2_P$2") (pintype "passive"))
      (node (ref "C32") (pin "P$2") (pinfunction "2_P$2") (pintype "passive"))
      (node (ref "C33") (pin "P$2") (pinfunction "2_P$2") (pintype "passive"))
      (node (ref "C34") (pin "P$2") (pinfunction "2_P$2") (pintype "passive"))
      (node (ref "C35") (pin "P$2") (pinfunction "2_P$2") (pintype "passive"))
      (node (ref "C36") (pin "P$2") (pinfunction "2_P$2") (pintype "passive"))
      (node (ref "C37") (pin "P$2") (pinfunction "2_P$2") (pintype "passive"))
      (node (ref "C38") (pin "P$2") (pinfunction "2_P$2") (pintype "passive"))
      (node (ref "C39") (pin "P$2") (pinfunction "2_P$2") (pintype "passive"))
      (node (ref "C6") (pin "2") (pinfunction "2_2") (pintype "passive"))
      (node (ref "FTDI") (pin "4") (pinfunction "VCC_4") (pintype "passive"))
      (node (ref "L1") (pin "1") (pinfunction "1_1") (pintype "passive"))
      (node (ref "LCD1") (pin "3") (pinfunction "VDD_3") (pintype "bidirectional"))
      (node (ref "LCD1") (pin "4") (pinfunction "VDDIO_4") (pintype "bidirectional"))
      (node (ref "LED1") (pin "2") (pinfunction "VDD_2") (pintype "power_in"))
      (node (ref "LED10") (pin "2") (pinfunction "VDD_2") (pintype "power_in"))
      (node (ref "LED11") (pin "2") (pinfunction "VDD_2") (pintype "power_in"))
      (node (ref "LED12") (pin "2") (pinfunction "VDD_2") (pintype "power_in"))
      (node (ref "LED13") (pin "2") (pinfunction "VDD_2") (pintype "power_in"))
      (node (ref "LED14") (pin "2") (pinfunction "VDD_2") (pintype "power_in"))
      (node (ref "LED2") (pin "2") (pinfunction "VDD_2") (pintype "power_in"))
      (node (ref "LED3") (pin "2") (pinfunction "VDD_2") (pintype "power_in"))
      (node (ref "LED4") (pin "2") (pinfunction "VDD_2") (pintype "power_in"))
      (node (ref "LED5") (pin "2") (pinfunction "VDD_2") (pintype "power_in"))
      (node (ref "LED6") (pin "2") (pinfunction "VDD_2") (pintype "power_in"))
      (node (ref "LED7") (pin "2") (pinfunction "VDD_2") (pintype "power_in"))
      (node (ref "LED8") (pin "2") (pinfunction "VDD_2") (pintype "power_in"))
      (node (ref "LED9") (pin "2") (pinfunction "VDD_2") (pintype "power_in"))
      (node (ref "R10") (pin "2") (pinfunction "2_2") (pintype "passive"))
      (node (ref "R2") (pin "2") (pinfunction "2_2") (pintype "passive"))
      (node (ref "R3") (pin "2") (pinfunction "2_2") (pintype "passive"))
      (node (ref "R8") (pin "1") (pinfunction "1_1") (pintype "passive"))
      (node (ref "S1") (pin "1") (pinfunction "1_1") (pintype "bidirectional"))
      (node (ref "U$2") (pin "1") (pinfunction "1_1") (pintype "passive"))
      (node (ref "U$2") (pin "2") (pinfunction "2_2") (pintype "passive"))
      (node (ref "U1") (pin "4") (pinfunction "SHDN_4") (pintype "bidirectional"))
      (node (ref "U1") (pin "5") (pinfunction "VIN_5") (pintype "bidirectional"))
      (node (ref "U2") (pin "1") (pinfunction "VDDA_1") (pintype "bidirectional"))
      (node (ref "U2") (pin "11") (pinfunction "VDDPST_11") (pintype "bidirectional"))
      (node (ref "U2") (pin "17") (pinfunction "VDDPST_17") (pintype "bidirectional"))
      (node (ref "U2") (pin "29") (pinfunction "VDDD_29") (pintype "bidirectional"))
      (node (ref "U2") (pin "3") (pinfunction "VDD3P3_3") (pintype "bidirectional"))
      (node (ref "U2") (pin "30") (pinfunction "VDDA_30") (pintype "bidirectional"))
      (node (ref "U2") (pin "4") (pinfunction "VDD3P3_4") (pintype "bidirectional"))
      (node (ref "U3") (pin "8") (pinfunction "VCC_8") (pintype "bidirectional"))
    )
    (net (code "48") (name "unconnected-(FTDI-CTS-Pad5)") (class "Default")
      (node (ref "FTDI") (pin "5") (pinfunction "CTS_5") (pintype "passive"))
    )
    (net (code "49") (name "unconnected-(FTDI-DTR-Pad1)") (class "Default")
      (node (ref "FTDI") (pin "1") (pinfunction "DTR_1") (pintype "passive"))
    )
    (net (code "50") (name "unconnected-(LCD1-D2-Pad15)") (class "Default")
      (node (ref "LCD1") (pin "15") (pinfunction "D2_15") (pintype "bidirectional"))
    )
    (net (code "51") (name "unconnected-(LCD1-D3-Pad16)") (class "Default")
      (node (ref "LCD1") (pin "16") (pinfunction "D3_16") (pintype "bidirectional"))
    )
    (net (code "52") (name "unconnected-(LCD1-D4-Pad17)") (class "Default")
      (node (ref "LCD1") (pin "17") (pinfunction "D4_17") (pintype "bidirectional"))
    )
    (net (code "53") (name "unconnected-(LCD1-D5-Pad18)") (class "Default")
      (node (ref "LCD1") (pin "18") (pinfunction "D5_18") (pintype "bidirectional"))
    )
    (net (code "54") (name "unconnected-(LCD1-D6-Pad19)") (class "Default")
      (node (ref "LCD1") (pin "19") (pinfunction "D6_19") (pintype "bidirectional"))
    )
    (net (code "55") (name "unconnected-(LCD1-D7-Pad20)") (class "Default")
      (node (ref "LCD1") (pin "20") (pinfunction "D7_20") (pintype "bidirectional"))
    )
    (net (code "56") (name "unconnected-(LCD1-E-Pad12)") (class "Default")
      (node (ref "LCD1") (pin "12") (pinfunction "E_12") (pintype "bidirectional"))
    )
    (net (code "57") (name "unconnected-(LCD1-NC1-Pad1)") (class "Default")
      (node (ref "LCD1") (pin "1") (pinfunction "NC1_1") (pintype "no_connect"))
    )
    (net (code "58") (name "unconnected-(LCD1-NC2-Pad23)") (class "Default")
      (node (ref "LCD1") (pin "23") (pinfunction "NC2_23") (pintype "no_connect"))
    )
    (net (code "59") (name "unconnected-(LCD1-R{slash}W#-Pad11)") (class "Default")
      (node (ref "LCD1") (pin "11") (pinfunction "R/W#_11") (pintype "bidirectional"))
    )
    (net (code "60") (name "unconnected-(LED14-DO-Pad3)") (class "Default")
      (node (ref "LED14") (pin "3") (pinfunction "DO_3") (pintype "output"))
    )
    (net (code "61") (name "unconnected-(S1-Pad3)") (class "Default")
      (node (ref "S1") (pin "3") (pinfunction "3_3") (pintype "bidirectional"))
    )
    (net (code "62") (name "unconnected-(S1-Pad4)") (class "Default")
      (node (ref "S1") (pin "4") (pinfunction "4_4") (pintype "bidirectional"))
    )
    (net (code "63") (name "unconnected-(S1-Pad5)") (class "Default")
      (node (ref "S1") (pin "5") (pinfunction "5_5") (pintype "bidirectional"))
    )
    (net (code "64") (name "unconnected-(S1-Pad6)") (class "Default")
      (node (ref "S1") (pin "6") (pinfunction "6_6") (pintype "bidirectional"))
    )
    (net (code "65") (name "unconnected-(U2-VDD_RTC-Pad5)") (class "Default")
      (node (ref "U2") (pin "5") (pinfunction "VDD_RTC_5") (pintype "bidirectional"))
    )
    (net (code "66") (name "unconnected-(U3-~{HOLD}(D3)-Pad7)") (class "Default")
      (node (ref "U3") (pin "7") (pinfunction "~{HOLD}(D3)_7") (pintype "bidirectional"))
    )
    (net (code "67") (name "unconnected-(U3-~{WP}(D2)-Pad3)") (class "Default")
      (node (ref "U3") (pin "3") (pinfunction "~{WP}(D2)_3") (pintype "bidirectional"))
    )
  )
)
